# IRF7314.net
KiCad netlist of a schematic drawn in Altium Designer
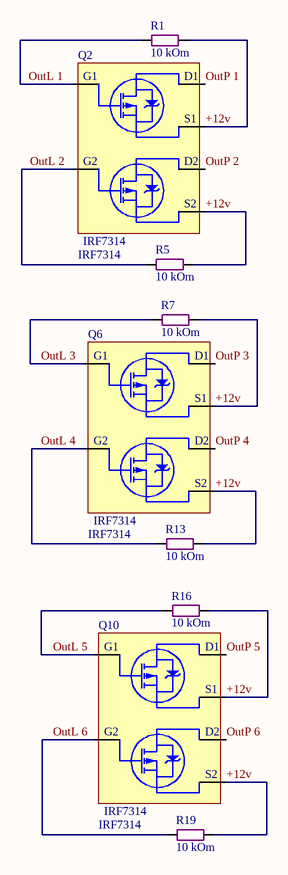
[diagram p0: IRF7314.SchDoc]

(export (version "E")
  (design (tool "Eeschema 10.0.6"))
  (components
    (comp (ref "Q2")
      (value "IRF7314")
      (footprint "GeneralCases:TSOP-6 (M)")
      (description "Dual P-Ch  20V - 0.135Ω - 2.2A")
      (libsource (lib "Transistor") (part "IRF5850"))
    )
    (comp (ref "Q6")
      (value "IRF7314")
      (footprint "GeneralCases:TSOP-6 (M)")
      (description "Dual P-Ch  20V - 0.135Ω - 2.2A")
      (libsource (lib "Transistor") (part "IRF5850"))
    )
    (comp (ref "Q10")
      (value "IRF7314")
      (footprint "GeneralCases:TSOP-6 (M)")
      (description "Dual P-Ch  20V - 0.135Ω - 2.2A")
      (libsource (lib "Transistor") (part "IRF5850"))
    )
    (comp (ref "R1")
      (value "10 kOm")
      (footprint "PassiveComponents:SMD 0603 (1608)")
      (libsource (lib "PassiveComponents") (part "Res All Types"))
    )
    (comp (ref "R5")
      (value "10 kOm")
      (footprint "PassiveComponents:SMD 0603 (1608)")
      (libsource (lib "PassiveComponents") (part "Res All Types"))
    )
    (comp (ref "R7")
      (value "10 kOm")
      (footprint "PassiveComponents:SMD 0603 (1608)")
      (libsource (lib "PassiveComponents") (part "Res All Types"))
    )
    (comp (ref "R13")
      (value "10 kOm")
      (footprint "PassiveComponents:SMD 0603 (1608)")
      (libsource (lib "PassiveComponents") (part "Res All Types"))
    )
    (comp (ref "R16")
      (value "10 kOm")
      (footprint "PassiveComponents:SMD 0603 (1608)")
      (libsource (lib "PassiveComponents") (part "Res All Types"))
    )
    (comp (ref "R19")
      (value "10 kOm")
      (footprint "PassiveComponents:SMD 0603 (1608)")
      (libsource (lib "PassiveComponents") (part "Res All Types"))
    )
  )
  (nets
    (net (code "1") (name "/+12v") (class "Default")
      (node (ref "Q10") (pin "2") (pinfunction "S2_2") (pintype "passive"))
      (node (ref "Q10") (pin "5") (pinfunction "S1_5") (pintype "passive"))
      (node (ref "Q2") (pin "2") (pinfunction "S2_2") (pintype "passive"))
      (node (ref "Q2") (pin "5") (pinfunction "S1_5") (pintype "passive"))
      (node (ref "Q6") (pin "2") (pinfunction "S2_2") (pintype "passive"))
      (node (ref "Q6") (pin "5") (pinfunction "S1_5") (pintype "passive"))
      (node (ref "R1") (pin "1") (pinfunction "1_1") (pintype "passive"))
      (node (ref "R13") (pin "1") (pinfunction "1_1") (pintype "passive"))
      (node (ref "R16") (pin "1") (pinfunction "1_1") (pintype "passive"))
      (node (ref "R19") (pin "1") (pinfunction "1_1") (pintype "passive"))
      (node (ref "R5") (pin "1") (pinfunction "1_1") (pintype "passive"))
      (node (ref "R7") (pin "1") (pinfunction "1_1") (pintype "passive"))
    )
    (net (code "2") (name "/OutL 1") (class "Default")
      (node (ref "Q2") (pin "1") (pinfunction "G1_1") (pintype "passive"))
      (node (ref "R1") (pin "2") (pinfunction "2_2") (pintype "passive"))
    )
    (net (code "3") (name "/OutL 2") (class "Default")
      (node (ref "Q2") (pin "3") (pinfunction "G2_3") (pintype "passive"))
      (node (ref "R5") (pin "2") (pinfunction "2_2") (pintype "passive"))
    )
    (net (code "4") (name "/OutL 3") (class "Default")
      (node (ref "Q6") (pin "1") (pinfunction "G1_1") (pintype "passive"))
      (node (ref "R7") (pin "2") (pinfunction "2_2") (pintype "passive"))
    )
    (net (code "5") (name "/OutL 4") (class "Default")
      (node (ref "Q6") (pin "3") (pinfunction "G2_3") (pintype "passive"))
      (node (ref "R13") (pin "2") (pinfunction "2_2") (pintype "passive"))
    )
    (net (code "6") (name "/OutL 5") (class "Default")
      (node (ref "Q10") (pin "1") (pinfunction "G1_1") (pintype "passive"))
      (node (ref "R16") (pin "2") (pinfunction "2_2") (pintype "passive"))
    )
    (net (code "7") (name "/OutL 6") (class "Default")
      (node (ref "Q10") (pin "3") (pinfunction "G2_3") (pintype "passive"))
      (node (ref "R19") (pin "2") (pinfunction "2_2") (pintype "passive"))
    )
    (net (code "8") (name "/OutP 1") (class "Default")
      (node (ref "Q2") (pin "6") (pinfunction "D1_6") (pintype "passive"))
    )
    (net (code "9") (name "/OutP 2") (class "Default")
      (node (ref "Q2") (pin "4") (pinfunction "D2_4") (pintype "passive"))
    )
    (net (code "10") (name "/OutP 3") (class "Default")
      (node (ref "Q6") (pin "6") (pinfunction "D1_6") (pintype "passive"))
    )
    (net (code "11") (name "/OutP 4") (class "Default")
      (node (ref "Q6") (pin "4") (pinfunction "D2_4") (pintype "passive"))
    )
    (net (code "12") (name "/OutP 5") (class "Default")
      (node (ref "Q10") (pin "6") (pinfunction "D1_6") (pintype "passive"))
    )
    (net (code "13") (name "/OutP 6") (class "Default")
      (node (ref "Q10") (pin "4") (pinfunction "D2_4") (pintype "passive"))
    )
  )
)
